# FRONT-UNIT.net
KiCad netlist of a schematic drawn in Altium Designer
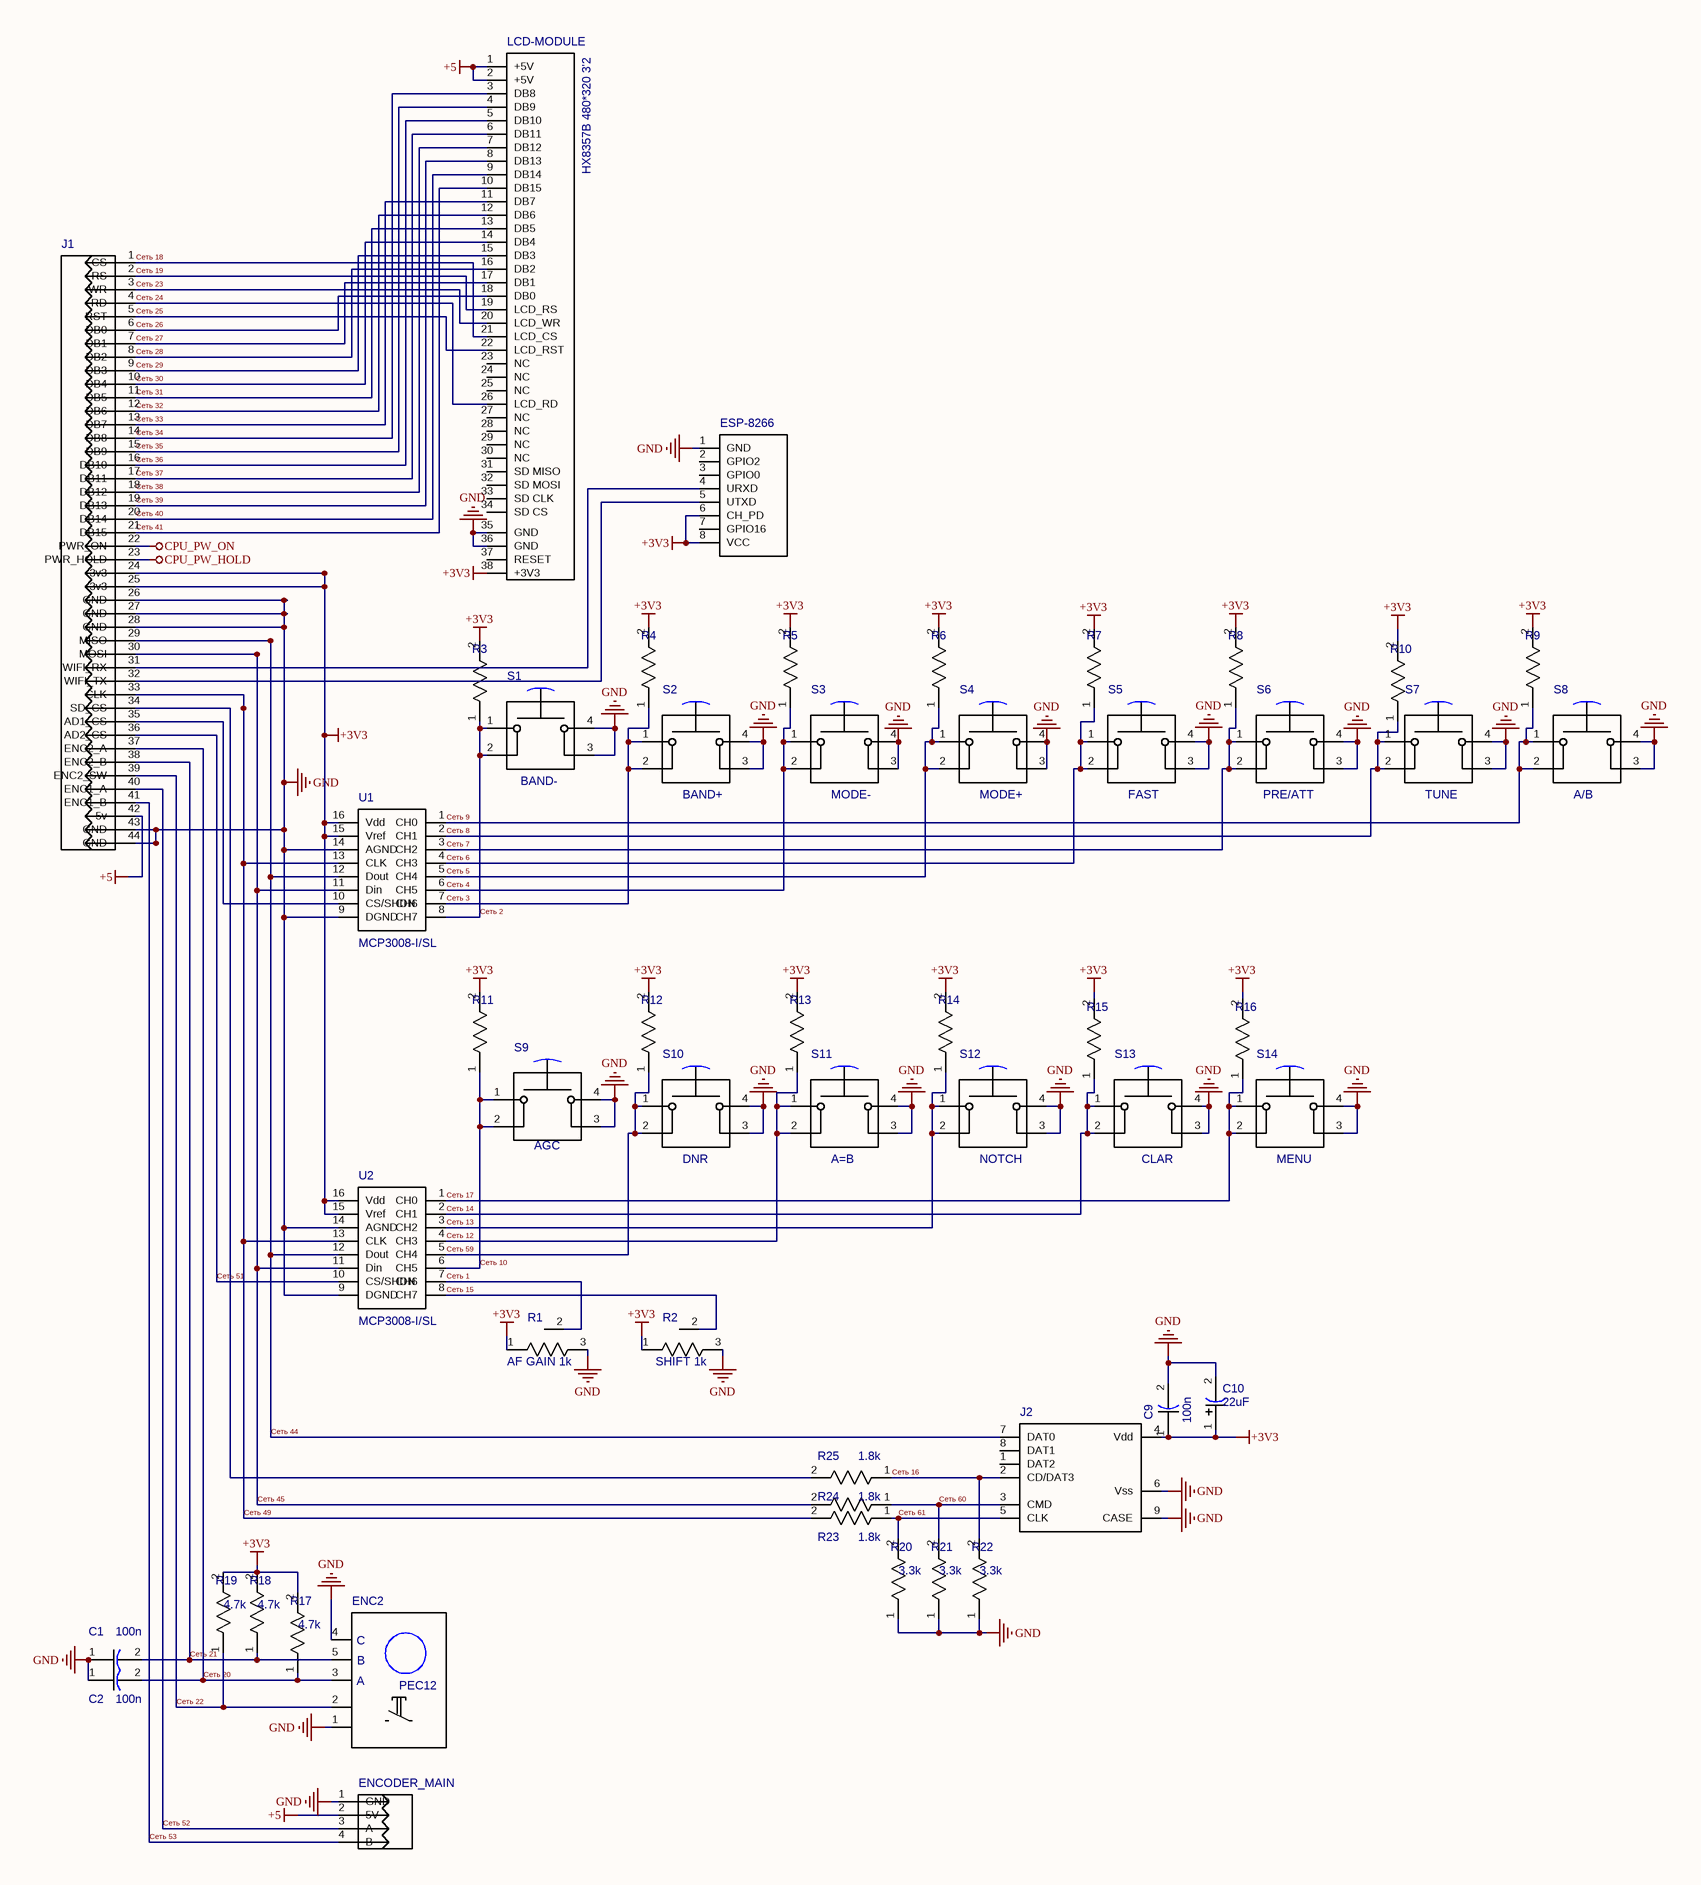
[diagram p0: FRONT-UNIT.SCHDOC, left]
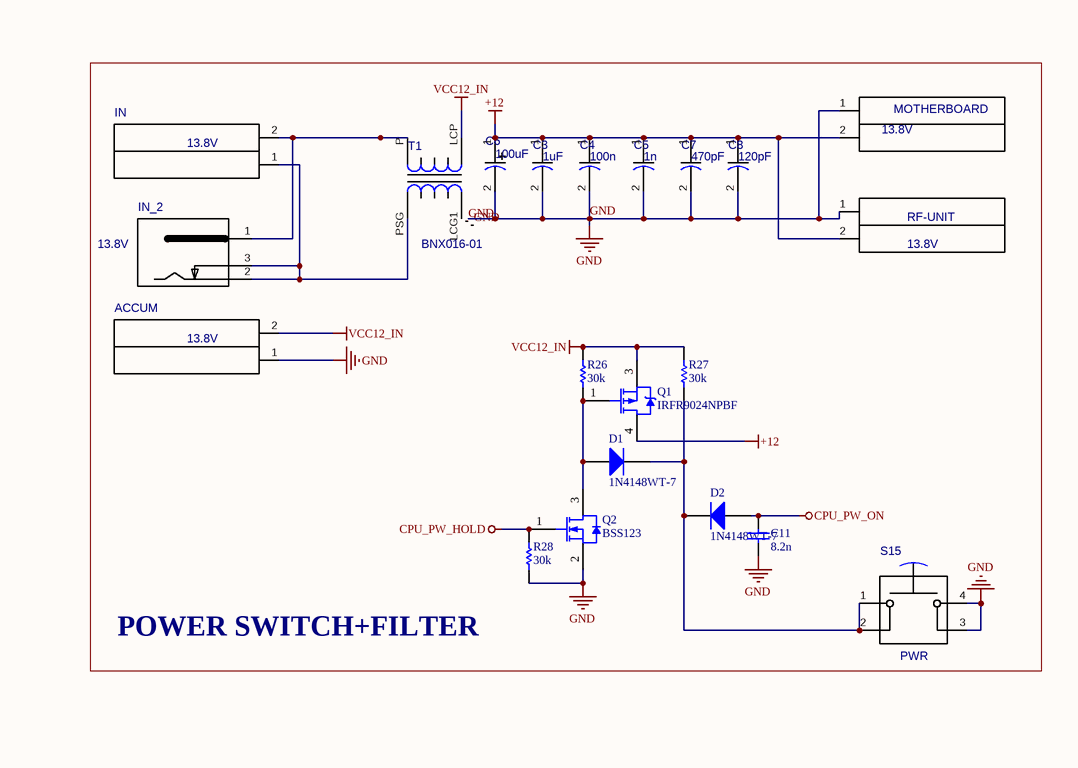
[diagram p1: FRONT-UNIT.SCHDOC, right]

(export (version "E")
  (design (tool "Eeschema 10.0.6"))
  (components
    (comp (ref "ACCUM")
      (value "13.8V")
      (footprint "JX2")
      (description "JX2")
      (libsource (lib "*") (part "JX2"))
    )
    (comp (ref "C1")
      (value "100n")
      (footprint "CAP_0805")
      (description "CAP_0805")
      (libsource (lib "*") (part "CAP_0805"))
    )
    (comp (ref "C2")
      (value "100n")
      (footprint "CAP_0805")
      (description "CAP_0805")
      (libsource (lib "*") (part "CAP_0805"))
    )
    (comp (ref "C3")
      (value "1uF")
      (footprint "CAP_1206")
      (description "CAP_1206")
      (libsource (lib "*") (part "CAP_1206"))
    )
    (comp (ref "C4")
      (value "100n")
      (footprint "CAP_1206")
      (description "CAP_1206")
      (libsource (lib "*") (part "CAP_1206"))
    )
    (comp (ref "C5")
      (value "1n")
      (footprint "CAP_1206")
      (description "CAP_1206")
      (libsource (lib "*") (part "CAP_1206"))
    )
    (comp (ref "C6")
      (value "100uF")
      (footprint "CAP250RP")
      (description "CAP250RP")
      (libsource (lib "*") (part "CAP250RP"))
    )
    (comp (ref "C7")
      (value "470pF")
      (footprint "CAP_1206")
      (description "CAP_1206")
      (libsource (lib "*") (part "CAP_1206"))
    )
    (comp (ref "C8")
      (value "120pF")
      (footprint "CAP_1206")
      (description "CAP_1206")
      (libsource (lib "*") (part "CAP_1206"))
    )
    (comp (ref "C9")
      (value "100n")
      (footprint "CAP_0805")
      (description "CAP_0805")
      (libsource (lib "*") (part "CAP_0805"))
    )
    (comp (ref "C10")
      (value "22uF")
      (footprint "EEEFC_sizeB")
      (description "EEEFC_sizeB")
      (libsource (lib "*") (part "EEEFC_sizeB"))
    )
    (comp (ref "C11")
      (value "8.2n")
      (footprint "CAPC2013X94X50LL20T25")
      (fields
        (field (name "MANUFACTURER") "AVX Interconnect / Elco")
        (field (name "PART NUMBER") "08055C822KAT2A")
      )
      (libsource (lib "Altium Content Vault") (part "CAP"))
    )
    (comp (ref "D1")
      (value "1N4148WT-7")
      (footprint "DIOD-SOD523-2_V")
      (description "Surface Mount Fast Switching Diode, -65 to 150 degC, 2-Pin SOD523, RoHS, Tape and Reel")
      (fields (field (name "MANUFACTURER") "Diodes Inc") (field (name "PARTNUMBER") "1N4148WT"))
      (libsource (lib "Altium Content Vault") (part "D-KA-2"))
    )
    (comp (ref "D2")
      (value "1N4148WT-7")
      (footprint "DIOD-SOD523-2_V")
      (description "Surface Mount Fast Switching Diode, -65 to 150 degC, 2-Pin SOD523, RoHS, Tape and Reel")
      (fields (field (name "MANUFACTURER") "Diodes Inc") (field (name "PARTNUMBER") "1N4148WT"))
      (libsource (lib "Altium Content Vault") (part "D-KA-2"))
    )
    (comp (ref "ENC2") (value "PEC12") (footprint "PEC12") (libsource (lib "*") (part "PEC12")))
    (comp (ref "ENCODER_MAIN")
      (value "644456-4")
      (footprint "644456-4")
      (libsource (lib "*") (part "644456-4"))
    )
    (comp (ref "ESP-8266")
      (value "ESP-01 ESP8266")
      (footprint "ESP-01 ESP8266")
      (libsource (lib "*") (part "ESP-01 ESP8266"))
    )
    (comp (ref "IN") (value "13.8V") (footprint "JX2") (description "JX2") (libsource (lib "*") (part "JX2")))
    (comp (ref "IN_2")
      (value "13.8V")
      (footprint "PJ-050B")
      (description "PJ-050B")
      (libsource (lib "*") (part "PJ-050B"))
    )
    (comp (ref "J1") (value "90131-0142") (footprint "90131-0142") (libsource (lib "*") (part "90131-0142")))
    (comp (ref "J2") (value "0472190001") (footprint "0472190001") (libsource (lib "*") (part "0472190001")))
    (comp (ref "LCD-MODULE")
      (value "HX8357B 480*320 3'2")
      (footprint "LCD-MODULE-3.2-480-320")
      (description "LCD-MODULE_3'2_480х320")
      (libsource (lib "FRONT-UNIT") (part "LCD-MODULE_3'2_480х320"))
    )
    (comp (ref "MOTHERBOARD")
      (value "13.8V")
      (footprint "JX2")
      (description "JX2")
      (libsource (lib "*") (part "JX2"))
    )
    (comp (ref "Q1")
      (value "IRFR9024NPBF")
      (footprint "ONSC-DPAK-3-369C-01_V")
      (description "IRFR9024NPBF, Транзистор, Р-канал 55В 11А")
      (fields (field (name "MANUFACTURER") "On Semiconductor") (field (name "PARTNUMBER") "NTD2955G"))
      (libsource (lib "Altium Content Vault") (part "ONSC-PMOS-G1S3D4-3_B"))
    )
    (comp (ref "Q2")
      (value "BSS123")
      (footprint "FAIR-SOT23-3_V")
      (fields (field (name "MANUFACTURER") "Fairchild"))
      (libsource (lib "Altium Content Vault") (part "NEMOS-GSD-3"))
    )
    (comp (ref "R1")
      (value "AF GAIN 1k")
      (footprint "PTV09")
      (description "Adjustable Resistor PTV09")
      (fields (field (name "Comment") "AF GAIN"))
      (libsource (lib "*") (part "PTV09"))
    )
    (comp (ref "R2")
      (value "SHIFT 1k")
      (footprint "PTV09")
      (description "Adjustable Resistor PTV09")
      (fields (field (name "Comment") "SHIFT"))
      (libsource (lib "*") (part "PTV09"))
    )
    (comp (ref "R3") (value "RES_0805") (footprint "RES_0805") (libsource (lib "*") (part "RES_0805")))
    (comp (ref "R4") (value "RES_0805") (footprint "RES_0805") (libsource (lib "*") (part "RES_0805")))
    (comp (ref "R5") (value "RES_0805") (footprint "RES_0805") (libsource (lib "*") (part "RES_0805")))
    (comp (ref "R6") (value "RES_0805") (footprint "RES_0805") (libsource (lib "*") (part "RES_0805")))
    (comp (ref "R7") (value "RES_0805") (footprint "RES_0805") (libsource (lib "*") (part "RES_0805")))
    (comp (ref "R8") (value "RES_0805") (footprint "RES_0805") (libsource (lib "*") (part "RES_0805")))
    (comp (ref "R9") (value "RES_0805") (footprint "RES_0805") (libsource (lib "*") (part "RES_0805")))
    (comp (ref "R10") (value "RES_0805") (footprint "RES_0805") (libsource (lib "*") (part "RES_0805")))
    (comp (ref "R11") (value "RES_0805") (footprint "RES_0805") (libsource (lib "*") (part "RES_0805")))
    (comp (ref "R12") (value "RES_0805") (footprint "RES_0805") (libsource (lib "*") (part "RES_0805")))
    (comp (ref "R13") (value "RES_0805") (footprint "RES_0805") (libsource (lib "*") (part "RES_0805")))
    (comp (ref "R14") (value "RES_0805") (footprint "RES_0805") (libsource (lib "*") (part "RES_0805")))
    (comp (ref "R15") (value "RES_0805") (footprint "RES_0805") (libsource (lib "*") (part "RES_0805")))
    (comp (ref "R16") (value "RES_0805") (footprint "RES_0805") (libsource (lib "*") (part "RES_0805")))
    (comp (ref "R17")
      (value "4.7k")
      (footprint "RES_0805")
      (description "RES_0805")
      (libsource (lib "*") (part "RES_0805"))
    )
    (comp (ref "R18")
      (value "4.7k")
      (footprint "RES_0805")
      (description "RES_0805")
      (libsource (lib "*") (part "RES_0805"))
    )
    (comp (ref "R19")
      (value "4.7k")
      (footprint "RES_0805")
      (description "RES_0805")
      (libsource (lib "*") (part "RES_0805"))
    )
    (comp (ref "R20")
      (value "3.3k")
      (footprint "RES_0805")
      (description "RES_0805")
      (libsource (lib "*") (part "RES_0805"))
    )
    (comp (ref "R21")
      (value "3.3k")
      (footprint "RES_0805")
      (description "RES_0805")
      (libsource (lib "*") (part "RES_0805"))
    )
    (comp (ref "R22")
      (value "3.3k")
      (footprint "RES_0805")
      (description "RES_0805")
      (libsource (lib "*") (part "RES_0805"))
    )
    (comp (ref "R23")
      (value "1.8k")
      (footprint "RES_0805")
      (description "RES_0805")
      (libsource (lib "*") (part "RES_0805"))
    )
    (comp (ref "R24")
      (value "1.8k")
      (footprint "RES_0805")
      (description "RES_0805")
      (libsource (lib "*") (part "RES_0805"))
    )
    (comp (ref "R25")
      (value "1.8k")
      (footprint "RES_0805")
      (description "RES_0805")
      (libsource (lib "*") (part "RES_0805"))
    )
    (comp (ref "R26")
      (value "30k")
      (footprint "RESC2013X60X40NL20T25")
      (fields (field (name "MANUFACTURER") "Panasonic") (field (name "PART NUMBER") "ERA-6AEB303V"))
      (libsource (lib "Altium Content Vault") (part "RES"))
    )
    (comp (ref "R27")
      (value "30k")
      (footprint "RESC2013X60X40NL20T25")
      (fields (field (name "MANUFACTURER") "Panasonic") (field (name "PART NUMBER") "ERA-6AEB303V"))
      (libsource (lib "Altium Content Vault") (part "RES"))
    )
    (comp (ref "R28")
      (value "30k")
      (footprint "RESC2013X60X40NL20T25")
      (fields (field (name "MANUFACTURER") "Panasonic") (field (name "PART NUMBER") "ERA-6AEB303V"))
      (libsource (lib "Altium Content Vault") (part "RES"))
    )
    (comp (ref "RF-UNIT")
      (value "13.8V")
      (footprint "JX2")
      (description "JX2")
      (libsource (lib "*") (part "JX2"))
    )
    (comp (ref "S1")
      (value "BAND-")
      (footprint "PTS645SK50LFS")
      (description "PTS645SK50LFS")
      (libsource (lib "*") (part "PTS645SK50LFS"))
    )
    (comp (ref "S2")
      (value "BAND+")
      (footprint "PTS645SK50LFS")
      (description "PTS645SK50LFS")
      (libsource (lib "*") (part "PTS645SK50LFS"))
    )
    (comp (ref "S3")
      (value "MODE-")
      (footprint "PTS645SK50LFS")
      (description "PTS645SK50LFS")
      (libsource (lib "*") (part "PTS645SK50LFS"))
    )
    (comp (ref "S4")
      (value "MODE+")
      (footprint "PTS645SK50LFS")
      (description "PTS645SK50LFS")
      (libsource (lib "*") (part "PTS645SK50LFS"))
    )
    (comp (ref "S5")
      (value "FAST")
      (footprint "PTS645SK50LFS")
      (description "PTS645SK50LFS")
      (libsource (lib "*") (part "PTS645SK50LFS"))
    )
    (comp (ref "S6")
      (value "PRE/ATT")
      (footprint "PTS645SK50LFS")
      (description "PTS645SK50LFS")
      (libsource (lib "*") (part "PTS645SK50LFS"))
    )
    (comp (ref "S7")
      (value "TUNE")
      (footprint "PTS645SK50LFS")
      (description "PTS645SK50LFS")
      (libsource (lib "*") (part "PTS645SK50LFS"))
    )
    (comp (ref "S8")
      (value "A/B")
      (footprint "PTS645SK50LFS")
      (description "PTS645SK50LFS")
      (libsource (lib "*") (part "PTS645SK50LFS"))
    )
    (comp (ref "S9")
      (value "AGC")
      (footprint "PTS645SK50LFS")
      (description "PTS645SK50LFS")
      (libsource (lib "*") (part "PTS645SK50LFS"))
    )
    (comp (ref "S10")
      (value "DNR")
      (footprint "PTS645SK50LFS")
      (description "PTS645SK50LFS")
      (libsource (lib "*") (part "PTS645SK50LFS"))
    )
    (comp (ref "S11")
      (value "A=B")
      (footprint "PTS645SK50LFS")
      (description "PTS645SK50LFS")
      (fields (field (name "Comment") "NOTCH"))
      (libsource (lib "*") (part "PTS645SK50LFS"))
    )
    (comp (ref "S12")
      (value "NOTCH")
      (footprint "PTS645SK50LFS")
      (description "PTS645SK50LFS")
      (libsource (lib "*") (part "PTS645SK50LFS"))
    )
    (comp (ref "S13")
      (value "CLAR")
      (footprint "PTS645SK50LFS")
      (description "PTS645SK50LFS")
      (libsource (lib "*") (part "PTS645SK50LFS"))
    )
    (comp (ref "S14")
      (value "MENU")
      (footprint "PTS645SK50LFS")
      (description "PTS645SK50LFS")
      (libsource (lib "*") (part "PTS645SK50LFS"))
    )
    (comp (ref "S15")
      (value "PWR")
      (footprint "PTS645SK50LFS")
      (description "PTS645SK50LFS")
      (libsource (lib "*") (part "PTS645SK50LFS"))
    )
    (comp (ref "T1")
      (value "BNX016-01")
      (footprint "TRANSF_ICORE")
      (description "Transformer")
      (fields (field (name "Comment") "TRANSF_ICORE"))
      (libsource (lib "*") (part "TRANSF_ICORE"))
    )
    (comp (ref "U1")
      (value "MCP3008-I/SL")
      (footprint "MCP3008-I/SL")
      (libsource (lib "*") (part "MCP3008-I/SL"))
    )
    (comp (ref "U2")
      (value "MCP3008-I/SL")
      (footprint "MCP3008-I/SL")
      (libsource (lib "*") (part "MCP3008-I/SL"))
    )
  )
  (nets
    (net (code "1") (name "+3V3") (class "Default")
      (node (ref "C10") (pin "1") (pinfunction "PLUS_1") (pintype "passive"))
      (node (ref "C9") (pin "1") (pinfunction "1_1") (pintype "passive"))
      (node (ref "ESP-8266") (pin "6") (pinfunction "CH_PD_6") (pintype "passive"))
      (node (ref "ESP-8266") (pin "8") (pinfunction "VCC_8") (pintype "passive"))
      (node (ref "J1") (pin "24") (pinfunction "3v3_24") (pintype "passive"))
      (node (ref "J1") (pin "25") (pinfunction "3v3_25") (pintype "passive"))
      (node (ref "J2") (pin "4") (pinfunction "Vdd_4") (pintype "passive"))
      (node (ref "LCD-MODULE") (pin "38") (pinfunction "+3V3_38") (pintype "passive"))
      (node (ref "R1") (pin "1") (pinfunction "CW_1") (pintype "passive"))
      (node (ref "R10") (pin "2") (pinfunction "2_2") (pintype "passive"))
      (node (ref "R11") (pin "2") (pinfunction "2_2") (pintype "passive"))
      (node (ref "R12") (pin "2") (pinfunction "2_2") (pintype "passive"))
      (node (ref "R13") (pin "2") (pinfunction "2_2") (pintype "passive"))
      (node (ref "R14") (pin "2") (pinfunction "2_2") (pintype "passive"))
      (node (ref "R15") (pin "2") (pinfunction "2_2") (pintype "passive"))
      (node (ref "R16") (pin "2") (pinfunction "2_2") (pintype "passive"))
      (node (ref "R17") (pin "2") (pinfunction "2_2") (pintype "passive"))
      (node (ref "R18") (pin "2") (pinfunction "2_2") (pintype "passive"))
      (node (ref "R19") (pin "2") (pinfunction "2_2") (pintype "passive"))
      (node (ref "R2") (pin "1") (pinfunction "CW_1") (pintype "passive"))
      (node (ref "R3") (pin "2") (pinfunction "2_2") (pintype "passive"))
      (node (ref "R4") (pin "2") (pinfunction "2_2") (pintype "passive"))
      (node (ref "R5") (pin "2") (pinfunction "2_2") (pintype "passive"))
      (node (ref "R6") (pin "2") (pinfunction "2_2") (pintype "passive"))
      (node (ref "R7") (pin "2") (pinfunction "2_2") (pintype "passive"))
      (node (ref "R8") (pin "2") (pinfunction "2_2") (pintype "passive"))
      (node (ref "R9") (pin "2") (pinfunction "2_2") (pintype "passive"))
      (node (ref "U1") (pin "15") (pinfunction "Vref_15") (pintype "passive"))
      (node (ref "U1") (pin "16") (pinfunction "Vdd_16") (pintype "passive"))
      (node (ref "U2") (pin "15") (pinfunction "Vref_15") (pintype "passive"))
      (node (ref "U2") (pin "16") (pinfunction "Vdd_16") (pintype "passive"))
    )
    (net (code "2") (name "+5") (class "Default")
      (node (ref "ENCODER_MAIN") (pin "2") (pinfunction "5V_2") (pintype "passive"))
      (node (ref "J1") (pin "42") (pinfunction "5v_42") (pintype "passive"))
      (node (ref "LCD-MODULE") (pin "1") (pinfunction "+5V_1") (pintype "passive"))
      (node (ref "LCD-MODULE") (pin "2") (pinfunction "+5V_2") (pintype "passive"))
    )
    (net (code "3") (name "+12") (class "Default")
      (node (ref "C3") (pin "1") (pinfunction "1_1") (pintype "passive"))
      (node (ref "C4") (pin "1") (pinfunction "1_1") (pintype "passive"))
      (node (ref "C5") (pin "1") (pinfunction "1_1") (pintype "passive"))
      (node (ref "C6") (pin "1") (pinfunction "PLUS_1") (pintype "passive"))
      (node (ref "C7") (pin "1") (pinfunction "1_1") (pintype "passive"))
      (node (ref "C8") (pin "1") (pinfunction "1_1") (pintype "passive"))
      (node (ref "MOTHERBOARD") (pin "2") (pinfunction "1_2") (pintype "passive"))
      (node (ref "Q1") (pin "4") (pinfunction "D_4") (pintype "passive"))
      (node (ref "RF-UNIT") (pin "2") (pinfunction "1_2") (pintype "passive"))
    )
    (net (code "4") (name "/Сеть 1") (class "Default")
      (node (ref "R1") (pin "2") (pinfunction "W_2") (pintype "passive"))
      (node (ref "U2") (pin "7") (pinfunction "CH6_7") (pintype "passive"))
    )
    (net (code "5") (name "/Сеть 2") (class "Default")
      (node (ref "R3") (pin "1") (pinfunction "1_1") (pintype "passive"))
      (node (ref "S1") (pin "1") (pinfunction "A_1") (pintype "passive"))
      (node (ref "S1") (pin "2") (pinfunction "A_2") (pintype "passive"))
      (node (ref "U1") (pin "8") (pinfunction "CH7_8") (pintype "passive"))
    )
    (net (code "6") (name "/Сеть 3") (class "Default")
      (node (ref "R4") (pin "1") (pinfunction "1_1") (pintype "passive"))
      (node (ref "S2") (pin "1") (pinfunction "A_1") (pintype "passive"))
      (node (ref "S2") (pin "2") (pinfunction "A_2") (pintype "passive"))
      (node (ref "U1") (pin "7") (pinfunction "CH6_7") (pintype "passive"))
    )
    (net (code "7") (name "/Сеть 4") (class "Default")
      (node (ref "R5") (pin "1") (pinfunction "1_1") (pintype "passive"))
      (node (ref "S3") (pin "1") (pinfunction "A_1") (pintype "passive"))
      (node (ref "S3") (pin "2") (pinfunction "A_2") (pintype "passive"))
      (node (ref "U1") (pin "6") (pinfunction "CH5_6") (pintype "passive"))
    )
    (net (code "8") (name "/Сеть 5") (class "Default")
      (node (ref "R6") (pin "1") (pinfunction "1_1") (pintype "passive"))
      (node (ref "S4") (pin "1") (pinfunction "A_1") (pintype "passive"))
      (node (ref "S4") (pin "2") (pinfunction "A_2") (pintype "passive"))
      (node (ref "U1") (pin "5") (pinfunction "CH4_5") (pintype "passive"))
    )
    (net (code "9") (name "/Сеть 6") (class "Default")
      (node (ref "R7") (pin "1") (pinfunction "1_1") (pintype "passive"))
      (node (ref "S5") (pin "1") (pinfunction "A_1") (pintype "passive"))
      (node (ref "S5") (pin "2") (pinfunction "A_2") (pintype "passive"))
      (node (ref "U1") (pin "4") (pinfunction "CH3_4") (pintype "passive"))
    )
    (net (code "10") (name "/Сеть 7") (class "Default")
      (node (ref "R8") (pin "1") (pinfunction "1_1") (pintype "passive"))
      (node (ref "S6") (pin "1") (pinfunction "A_1") (pintype "passive"))
      (node (ref "S6") (pin "2") (pinfunction "A_2") (pintype "passive"))
      (node (ref "U1") (pin "3") (pinfunction "CH2_3") (pintype "passive"))
    )
    (net (code "11") (name "/Сеть 8") (class "Default")
      (node (ref "R10") (pin "1") (pinfunction "1_1") (pintype "passive"))
      (node (ref "S7") (pin "1") (pinfunction "A_1") (pintype "passive"))
      (node (ref "S7") (pin "2") (pinfunction "A_2") (pintype "passive"))
      (node (ref "U1") (pin "2") (pinfunction "CH1_2") (pintype "passive"))
    )
    (net (code "12") (name "/Сеть 9") (class "Default")
      (node (ref "R9") (pin "1") (pinfunction "1_1") (pintype "passive"))
      (node (ref "S8") (pin "1") (pinfunction "A_1") (pintype "passive"))
      (node (ref "S8") (pin "2") (pinfunction "A_2") (pintype "passive"))
      (node (ref "U1") (pin "1") (pinfunction "CH0_1") (pintype "passive"))
    )
    (net (code "13") (name "/Сеть 10") (class "Default")
      (node (ref "R11") (pin "1") (pinfunction "1_1") (pintype "passive"))
      (node (ref "S9") (pin "1") (pinfunction "A_1") (pintype "passive"))
      (node (ref "S9") (pin "2") (pinfunction "A_2") (pintype "passive"))
      (node (ref "U2") (pin "6") (pinfunction "CH5_6") (pintype "passive"))
    )
    (net (code "14") (name "/Сеть 12") (class "Default")
      (node (ref "R13") (pin "1") (pinfunction "1_1") (pintype "passive"))
      (node (ref "S11") (pin "1") (pinfunction "A_1") (pintype "passive"))
      (node (ref "S11") (pin "2") (pinfunction "A_2") (pintype "passive"))
      (node (ref "U2") (pin "4") (pinfunction "CH3_4") (pintype "passive"))
    )
    (net (code "15") (name "/Сеть 13") (class "Default")
      (node (ref "R14") (pin "1") (pinfunction "1_1") (pintype "passive"))
      (node (ref "S12") (pin "1") (pinfunction "A_1") (pintype "passive"))
      (node (ref "S12") (pin "2") (pinfunction "A_2") (pintype "passive"))
      (node (ref "U2") (pin "3") (pinfunction "CH2_3") (pintype "passive"))
    )
    (net (code "16") (name "/Сеть 14") (class "Default")
      (node (ref "R15") (pin "1") (pinfunction "1_1") (pintype "passive"))
      (node (ref "S13") (pin "1") (pinfunction "A_1") (pintype "passive"))
      (node (ref "S13") (pin "2") (pinfunction "A_2") (pintype "passive"))
      (node (ref "U2") (pin "2") (pinfunction "CH1_2") (pintype "passive"))
    )
    (net (code "17") (name "/Сеть 15") (class "Default")
      (node (ref "R2") (pin "2") (pinfunction "W_2") (pintype "passive"))
      (node (ref "U2") (pin "8") (pinfunction "CH7_8") (pintype "passive"))
    )
    (net (code "18") (name "/Сеть 16") (class "Default")
      (node (ref "J2") (pin "2") (pinfunction "CD/DAT3_2") (pintype "passive"))
      (node (ref "R22") (pin "2") (pinfunction "2_2") (pintype "passive"))
      (node (ref "R25") (pin "1") (pinfunction "1_1") (pintype "passive"))
    )
    (net (code "19") (name "/Сеть 17") (class "Default")
      (node (ref "R16") (pin "1") (pinfunction "1_1") (pintype "passive"))
      (node (ref "S14") (pin "1") (pinfunction "A_1") (pintype "passive"))
      (node (ref "S14") (pin "2") (pinfunction "A_2") (pintype "passive"))
      (node (ref "U2") (pin "1") (pinfunction "CH0_1") (pintype "passive"))
    )
    (net (code "20") (name "/Сеть 18") (class "Default")
      (node (ref "J1") (pin "1") (pinfunction "CS_1") (pintype "passive"))
      (node (ref "LCD-MODULE") (pin "21") (pinfunction "LCD_CS_21") (pintype "passive"))
    )
    (net (code "21") (name "/Сеть 19") (class "Default")
      (node (ref "J1") (pin "2") (pinfunction "RS_2") (pintype "passive"))
      (node (ref "LCD-MODULE") (pin "19") (pinfunction "LCD_RS_19") (pintype "passive"))
    )
    (net (code "22") (name "/Сеть 20") (class "Default")
      (node (ref "C2") (pin "2") (pinfunction "2_2") (pintype "passive"))
      (node (ref "ENC2") (pin "3") (pinfunction "A_3") (pintype "passive"))
      (node (ref "J1") (pin "37") (pinfunction "ENC2_A_37") (pintype "passive"))
      (node (ref "R17") (pin "1") (pinfunction "1_1") (pintype "passive"))
    )
    (net (code "23") (name "/Сеть 21") (class "Default")
      (node (ref "C1") (pin "2") (pinfunction "2_2") (pintype "passive"))
      (node (ref "ENC2") (pin "5") (pinfunction "B_5") (pintype "passive"))
      (node (ref "J1") (pin "38") (pinfunction "ENC2_B_38") (pintype "passive"))
      (node (ref "R18") (pin "1") (pinfunction "1_1") (pintype "passive"))
    )
    (net (code "24") (name "/Сеть 22") (class "Default")
      (node (ref "ENC2") (pin "2") (pinfunction "2_2") (pintype "passive"))
      (node (ref "J1") (pin "39") (pinfunction "ENC2_SW_39") (pintype "passive"))
      (node (ref "R19") (pin "1") (pinfunction "1_1") (pintype "passive"))
    )
    (net (code "25") (name "/Сеть 23") (class "Default")
      (node (ref "J1") (pin "3") (pinfunction "WR_3") (pintype "passive"))
      (node (ref "LCD-MODULE") (pin "20") (pinfunction "LCD_WR_20") (pintype "passive"))
    )
    (net (code "26") (name "/Сеть 24") (class "Default")
      (node (ref "J1") (pin "4") (pinfunction "RD_4") (pintype "passive"))
      (node (ref "LCD-MODULE") (pin "26") (pinfunction "LCD_RD_26") (pintype "passive"))
    )
    (net (code "27") (name "/Сеть 25") (class "Default")
      (node (ref "J1") (pin "5") (pinfunction "RST_5") (pintype "passive"))
      (node (ref "LCD-MODULE") (pin "22") (pinfunction "LCD_RST_22") (pintype "passive"))
    )
    (net (code "28") (name "/Сеть 26") (class "Default")
      (node (ref "J1") (pin "6") (pinfunction "DB0_6") (pintype "passive"))
      (node (ref "LCD-MODULE") (pin "18") (pinfunction "DB0_18") (pintype "passive"))
    )
    (net (code "29") (name "/Сеть 27") (class "Default")
      (node (ref "J1") (pin "7") (pinfunction "DB1_7") (pintype "passive"))
      (node (ref "LCD-MODULE") (pin "17") (pinfunction "DB1_17") (pintype "passive"))
    )
    (net (code "30") (name "/Сеть 28") (class "Default")
      (node (ref "J1") (pin "8") (pinfunction "DB2_8") (pintype "passive"))
      (node (ref "LCD-MODULE") (pin "16") (pinfunction "DB2_16") (pintype "passive"))
    )
    (net (code "31") (name "/Сеть 29") (class "Default")
      (node (ref "J1") (pin "9") (pinfunction "DB3_9") (pintype "passive"))
      (node (ref "LCD-MODULE") (pin "15") (pinfunction "DB3_15") (pintype "passive"))
    )
    (net (code "32") (name "/Сеть 30") (class "Default")
      (node (ref "J1") (pin "10") (pinfunction "DB4_10") (pintype "passive"))
      (node (ref "LCD-MODULE") (pin "14") (pinfunction "DB4_14") (pintype "passive"))
    )
    (net (code "33") (name "/Сеть 31") (class "Default")
      (node (ref "J1") (pin "11") (pinfunction "DB5_11") (pintype "passive"))
      (node (ref "LCD-MODULE") (pin "13") (pinfunction "DB5_13") (pintype "passive"))
    )
    (net (code "34") (name "/Сеть 32") (class "Default")
      (node (ref "J1") (pin "12") (pinfunction "DB6_12") (pintype "passive"))
      (node (ref "LCD-MODULE") (pin "12") (pinfunction "DB6_12") (pintype "passive"))
    )
    (net (code "35") (name "/Сеть 33") (class "Default")
      (node (ref "J1") (pin "13") (pinfunction "DB7_13") (pintype "passive"))
      (node (ref "LCD-MODULE") (pin "11") (pinfunction "DB7_11") (pintype "passive"))
    )
    (net (code "36") (name "/Сеть 34") (class "Default")
      (node (ref "J1") (pin "14") (pinfunction "DB8_14") (pintype "passive"))
      (node (ref "LCD-MODULE") (pin "3") (pinfunction "DB8_3") (pintype "passive"))
    )
    (net (code "37") (name "/Сеть 35") (class "Default")
      (node (ref "J1") (pin "15") (pinfunction "DB9_15") (pintype "passive"))
      (node (ref "LCD-MODULE") (pin "4") (pinfunction "DB9_4") (pintype "passive"))
    )
    (net (code "38") (name "/Сеть 36") (class "Default")
      (node (ref "J1") (pin "16") (pinfunction "DB10_16") (pintype "passive"))
      (node (ref "LCD-MODULE") (pin "5") (pinfunction "DB10_5") (pintype "passive"))
    )
    (net (code "39") (name "/Сеть 37") (class "Default")
      (node (ref "J1") (pin "17") (pinfunction "DB11_17") (pintype "passive"))
      (node (ref "LCD-MODULE") (pin "6") (pinfunction "DB11_6") (pintype "passive"))
    )
    (net (code "40") (name "/Сеть 38") (class "Default")
      (node (ref "J1") (pin "18") (pinfunction "DB12_18") (pintype "passive"))
      (node (ref "LCD-MODULE") (pin "7") (pinfunction "DB12_7") (pintype "passive"))
    )
    (net (code "41") (name "/Сеть 39") (class "Default")
      (node (ref "J1") (pin "19") (pinfunction "DB13_19") (pintype "passive"))
      (node (ref "LCD-MODULE") (pin "8") (pinfunction "DB13_8") (pintype "passive"))
    )
    (net (code "42") (name "/Сеть 40") (class "Default")
      (node (ref "J1") (pin "20") (pinfunction "DB14_20") (pintype "passive"))
      (node (ref "LCD-MODULE") (pin "9") (pinfunction "DB14_9") (pintype "passive"))
    )
    (net (code "43") (name "/Сеть 41") (class "Default")
      (node (ref "J1") (pin "21") (pinfunction "DB15_21") (pintype "passive"))
      (node (ref "LCD-MODULE") (pin "10") (pinfunction "DB15_10") (pintype "passive"))
    )
    (net (code "44") (name "/Сеть 44") (class "Default")
      (node (ref "J1") (pin "29") (pinfunction "MISO_29") (pintype "passive"))
      (node (ref "J2") (pin "7") (pinfunction "DAT0_7") (pintype "passive"))
      (node (ref "U1") (pin "12") (pinfunction "Dout_12") (pintype "passive"))
      (node (ref "U2") (pin "12") (pinfunction "Dout_12") (pintype "passive"))
    )
    (net (code "45") (name "/Сеть 45") (class "Default")
      (node (ref "J1") (pin "30") (pinfunction "MOSI_30") (pintype "passive"))
      (node (ref "R24") (pin "2") (pinfunction "2_2") (pintype "passive"))
      (node (ref "U1") (pin "11") (pinfunction "Din_11") (pintype "passive"))
      (node (ref "U2") (pin "11") (pinfunction "Din_11") (pintype "passive"))
    )
    (net (code "46") (name "/Сеть 49") (class "Default")
      (node (ref "J1") (pin "33") (pinfunction "CLK_33") (pintype "passive"))
      (node (ref "R23") (pin "2") (pinfunction "2_2") (pintype "passive"))
      (node (ref "U1") (pin "13") (pinfunction "CLK_13") (pintype "passive"))
      (node (ref "U2") (pin "13") (pinfunction "CLK_13") (pintype "passive"))
    )
    (net (code "47") (name "/Сеть 51") (class "Default")
      (node (ref "J1") (pin "36") (pinfunction "AD2_CS_36") (pintype "passive"))
      (node (ref "U2") (pin "10") (pinfunction "CS/SHDN_10") (pintype "passive"))
    )
    (net (code "48") (name "/Сеть 52") (class "Default")
      (node (ref "ENCODER_MAIN") (pin "3") (pinfunction "A_3") (pintype "passive"))
      (node (ref "J1") (pin "40") (pinfunction "ENC1_A_40") (pintype "passive"))
    )
    (net (code "49") (name "/Сеть 53") (class "Default")
      (node (ref "ENCODER_MAIN") (pin "4") (pinfunction "B_4") (pintype "passive"))
      (node (ref "J1") (pin "41") (pinfunction "ENC1_B_41") (pintype "passive"))
    )
    (net (code "50") (name "/Сеть 59") (class "Default")
      (node (ref "R12") (pin "1") (pinfunction "1_1") (pintype "passive"))
      (node (ref "S10") (pin "1") (pinfunction "A_1") (pintype "passive"))
      (node (ref "S10") (pin "2") (pinfunction "A_2") (pintype "passive"))
      (node (ref "U2") (pin "5") (pinfunction "CH4_5") (pintype "passive"))
    )
    (net (code "51") (name "/Сеть 60") (class "Default")
      (node (ref "J2") (pin "3") (pinfunction "CMD_3") (pintype "passive"))
      (node (ref "R21") (pin "2") (pinfunction "2_2") (pintype "passive"))
      (node (ref "R24") (pin "1") (pinfunction "1_1") (pintype "passive"))
    )
    (net (code "52") (name "/Сеть 61") (class "Default")
      (node (ref "J2") (pin "5") (pinfunction "CLK_5") (pintype "passive"))
      (node (ref "R20") (pin "2") (pinfunction "2_2") (pintype "passive"))
      (node (ref "R23") (pin "1") (pinfunction "1_1") (pintype "passive"))
    )
    (net (code "53") (name "CPU_PW_HOLD") (class "Default")
      (node (ref "J1") (pin "23") (pinfunction "PWR_HOLD_23") (pintype "passive"))
      (node (ref "Q2") (pin "1") (pinfunction "G_1") (pintype "passive"))
      (node (ref "R28") (pin "2") (pinfunction "2_2") (pintype "passive"))
    )
    (net (code "54") (name "CPU_PW_ON") (class "Default")
      (node (ref "C11") (pin "2") (pinfunction "2_2") (pintype "passive"))
      (node (ref "D2") (pin "2") (pinfunction "A_2") (pintype "passive"))
      (node (ref "J1") (pin "22") (pinfunction "PWR_ON_22") (pintype "passive"))
    )
    (net (code "55") (name "GND") (class "Default")
      (node (ref "ACCUM") (pin "1") (pinfunction "2_1") (pintype "passive"))
      (node (ref "C1") (pin "1") (pinfunction "1_1") (pintype "passive"))
      (node (ref "C10") (pin "2") (pinfunction "MINUS_2") (pintype "passive"))
      (node (ref "C11") (pin "1") (pinfunction "1_1") (pintype "passive"))
      (node (ref "C2") (pin "1") (pinfunction "1_1") (pintype "passive"))
      (node (ref "C3") (pin "2") (pinfunction "2_2") (pintype "passive"))
      (node (ref "C4") (pin "2") (pinfunction "2_2") (pintype "passive"))
      (node (ref "C5") (pin "2") (pinfunction "2_2") (pintype "passive"))
      (node (ref "C6") (pin "2") (pinfunction "MINUS_2") (pintype "passive"))
      (node (ref "C7") (pin "2") (pinfunction "2_2") (pintype "passive"))
      (node (ref "C8") (pin "2") (pinfunction "2_2") (pintype "passive"))
      (node (ref "C9") (pin "2") (pinfunction "2_2") (pintype "passive"))
      (node (ref "ENC2") (pin "1") (pinfunction "1_1") (pintype "passive"))
      (node (ref "ENC2") (pin "4") (pinfunction "C_4") (pintype "passive"))
      (node (ref "ENCODER_MAIN") (pin "1") (pinfunction "GND_1") (pintype "passive"))
      (node (ref "ESP-8266") (pin "1") (pinfunction "GND_1") (pintype "passive"))
      (node (ref "J1") (pin "26") (pinfunction "GND_26") (pintype "passive"))
      (node (ref "J1") (pin "27") (pinfunction "GND_27") (pintype "passive"))
      (node (ref "J1") (pin "28") (pinfunction "GND_28") (pintype "passive"))
      (node (ref "J1") (pin "43") (pinfunction "GND_43") (pintype "passive"))
      (node (ref "J1") (pin "44") (pinfunction "GND_44") (pintype "passive"))
      (node (ref "J2") (pin "6") (pinfunction "Vss_6") (pintype "passive"))
      (node (ref "J2") (pin "9") (pinfunction "CASE_9") (pintype "passive"))
      (node (ref "LCD-MODULE") (pin "35") (pinfunction "GND_35") (pintype "passive"))
      (node (ref "LCD-MODULE") (pin "36") (pinfunction "GND_36") (pintype "passive"))
      (node (ref "MOTHERBOARD") (pin "1") (pinfunction "2_1") (pintype "passive"))
      (node (ref "Q2") (pin "2") (pinfunction "S_2") (pintype "passive"))
      (node (ref "R1") (pin "3") (pinfunction "CCW_3") (pintype "passive"))
      (node (ref "R2") (pin "3") (pinfunction "CCW_3") (pintype "passive"))
      (node (ref "R20") (pin "1") (pinfunction "1_1") (pintype "passive"))
      (node (ref "R21") (pin "1") (pinfunction "1_1") (pintype "passive"))
      (node (ref "R22") (pin "1") (pinfunction "1_1") (pintype "passive"))
      (node (ref "R28") (pin "1") (pinfunction "1_1") (pintype "passive"))
      (node (ref "RF-UNIT") (pin "1") (pinfunction "2_1") (pintype "passive"))
      (node (ref "S1") (pin "3") (pinfunction "B_3") (pintype "passive"))
      (node (ref "S1") (pin "4") (pinfunction "B_4") (pintype "passive"))
      (node (ref "S10") (pin "3") (pinfunction "B_3") (pintype "passive"))
      (node (ref "S10") (pin "4") (pinfunction "B_4") (pintype "passive"))
      (node (ref "S11") (pin "3") (pinfunction "B_3") (pintype "passive"))
      (node (ref "S11") (pin "4") (pinfunction "B_4") (pintype "passive"))
      (node (ref "S12") (pin "3") (pinfunction "B_3") (pintype "passive"))
      (node (ref "S12") (pin "4") (pinfunction "B_4") (pintype "passive"))
      (node (ref "S13") (pin "3") (pinfunction "B_3") (pintype "passive"))
      (node (ref "S13") (pin "4") (pinfunction "B_4") (pintype "passive"))
      (node (ref "S14") (pin "3") (pinfunction "B_3") (pintype "passive"))
      (node (ref "S14") (pin "4") (pinfunction "B_4") (pintype "passive"))
      (node (ref "S15") (pin "3") (pinfunction "B_3") (pintype "passive"))
      (node (ref "S15") (pin "4") (pinfunction "B_4") (pintype "passive"))
      (node (ref "S2") (pin "3") (pinfunction "B_3") (pintype "passive"))
      (node (ref "S2") (pin "4") (pinfunction "B_4") (pintype "passive"))
      (node (ref "S3") (pin "3") (pinfunction "B_3") (pintype "passive"))
      (node (ref "S3") (pin "4") (pinfunction "B_4") (pintype "passive"))
      (node (ref "S4") (pin "3") (pinfunction "B_3") (pintype "passive"))
      (node (ref "S4") (pin "4") (pinfunction "B_4") (pintype "passive"))
      (node (ref "S5") (pin "3") (pinfunction "B_3") (pintype "passive"))
      (node (ref "S5") (pin "4") (pinfunction "B_4") (pintype "passive"))
      (node (ref "S6") (pin "3") (pinfunction "B_3") (pintype "passive"))
      (node (ref "S6") (pin "4") (pinfunction "B_4") (pintype "passive"))
      (node (ref "S7") (pin "3") (pinfunction "B_3") (pintype "passive"))
      (node (ref "S7") (pin "4") (pinfunction "B_4") (pintype "passive"))
      (node (ref "S8") (pin "3") (pinfunction "B_3") (pintype "passive"))
      (node (ref "S8") (pin "4") (pinfunction "B_4") (pintype "passive"))
      (node (ref "S9") (pin "3") (pinfunction "B_3") (pintype "passive"))
      (node (ref "S9") (pin "4") (pinfunction "B_4") (pintype "passive"))
      (node (ref "T1") (pin "LCG2") (pinfunction "0_LCG2") (pintype "passive"))
      (node (ref "T1") (pin "LCG3") (pinfunction "0_LCG3") (pintype "passive"))
      (node (ref "U1") (pin "14") (pinfunction "AGND_14") (pintype "passive"))
      (node (ref "U1") (pin "9") (pinfunction "DGND_9") (pintype "passive"))
      (node (ref "U2") (pin "14") (pinfunction "AGND_14") (pintype "passive"))
      (node (ref "U2") (pin "9") (pinfunction "DGND_9") (pintype "passive"))
    )
    (net (code "56") (name "Net-(D1-A)") (class "Default")
      (node (ref "D1") (pin "2") (pinfunction "A_2") (pintype "passive"))
      (node (ref "Q1") (pin "1") (pinfunction "G_1") (pintype "passive"))
      (node (ref "Q2") (pin "3") (pinfunction "D_3") (pintype "passive"))
      (node (ref "R26") (pin "1") (pinfunction "1_1") (pintype "passive"))
    )
    (net (code "57") (name "Net-(D1-K)") (class "Default")
      (node (ref "D1") (pin "1") (pinfunction "K_1") (pintype "passive"))
      (node (ref "D2") (pin "1") (pinfunction "K_1") (pintype "passive"))
      (node (ref "R27") (pin "1") (pinfunction "1_1") (pintype "passive"))
      (node (ref "S15") (pin "1") (pinfunction "A_1") (pintype "passive"))
      (node (ref "S15") (pin "2") (pinfunction "A_2") (pintype "passive"))
    )
    (net (code "58") (name "Net-(ESP-8266-URXD)") (class "Default")
      (node (ref "ESP-8266") (pin "4") (pinfunction "URXD_4") (pintype "passive"))
      (node (ref "J1") (pin "31") (pinfunction "WIFI_RX_31") (pintype "passive"))
    )
    (net (code "59") (name "Net-(ESP-8266-UTXD)") (class "Default")
      (node (ref "ESP-8266") (pin "5") (pinfunction "UTXD_5") (pintype "passive"))
      (node (ref "J1") (pin "32") (pinfunction "WIFI_TX_32") (pintype "passive"))
    )
    (net (code "60") (name "Net-(IN-1)") (class "Default")
      (node (ref "IN") (pin "2") (pinfunction "1_2") (pintype "passive"))
      (node (ref "IN_2") (pin "1") (pinfunction "1_1") (pintype "passive"))
      (node (ref "T1") (pin "P") (pinfunction "P1_P") (pintype "passive"))
    )
    (net (code "61") (name "Net-(IN-2)") (class "Default")
      (node (ref "IN") (pin "1") (pinfunction "2_1") (pintype "passive"))
      (node (ref "IN_2") (pin "2") (pinfunction "2_2") (pintype "passive"))
      (node (ref "IN_2") (pin "3") (pinfunction "3_3") (pintype "passive"))
      (node (ref "T1") (pin "PSG") (pinfunction "S1_PSG") (pintype "passive"))
    )
    (net (code "62") (name "Net-(J1-AD1_CS)") (class "Default")
      (node (ref "J1") (pin "35") (pinfunction "AD1_CS_35") (pintype "passive"))
      (node (ref "U1") (pin "10") (pinfunction "CS/SHDN_10") (pintype "passive"))
    )
    (net (code "63") (name "Net-(J1-SD_CS)") (class "Default")
      (node (ref "J1") (pin "34") (pinfunction "SD_CS_34") (pintype "passive"))
      (node (ref "R25") (pin "2") (pinfunction "2_2") (pintype "passive"))
    )
    (net (code "64") (name "VCC12_IN") (class "Default")
      (node (ref "ACCUM") (pin "2") (pinfunction "1_2") (pintype "passive"))
      (node (ref "Q1") (pin "3") (pinfunction "S_3") (pintype "passive"))
      (node (ref "R26") (pin "2") (pinfunction "2_2") (pintype "passive"))
      (node (ref "R27") (pin "2") (pinfunction "2_2") (pintype "passive"))
      (node (ref "T1") (pin "LCP") (pinfunction "P2_LCP") (pintype "passive"))
    )
    (net (code "65") (name "unconnected-(ESP-8266-GPIO0-Pad3)") (class "Default")
      (node (ref "ESP-8266") (pin "3") (pinfunction "GPIO0_3") (pintype "passive"))
    )
    (net (code "66") (name "unconnected-(ESP-8266-GPIO2-Pad2)") (class "Default")
      (node (ref "ESP-8266") (pin "2") (pinfunction "GPIO2_2") (pintype "passive"))
    )
    (net (code "67") (name "unconnected-(ESP-8266-GPIO16-Pad7)") (class "Default")
      (node (ref "ESP-8266") (pin "7") (pinfunction "GPIO16_7") (pintype "passive"))
    )
    (net (code "68") (name "unconnected-(J2-DAT1-Pad8)") (class "Default")
      (node (ref "J2") (pin "8") (pinfunction "DAT1_8") (pintype "passive"))
    )
    (net (code "69") (name "unconnected-(J2-DAT2-Pad1)") (class "Default")
      (node (ref "J2") (pin "1") (pinfunction "DAT2_1") (pintype "passive"))
    )
    (net (code "70") (name "unconnected-(LCD-MODULE-NC-Pad23)") (class "Default")
      (node (ref "LCD-MODULE") (pin "23") (pinfunction "NC_23") (pintype "passive"))
    )
    (net (code "71") (name "unconnected-(LCD-MODULE-NC-Pad24)") (class "Default")
      (node (ref "LCD-MODULE") (pin "24") (pinfunction "NC_24") (pintype "passive"))
    )
    (net (code "72") (name "unconnected-(LCD-MODULE-NC-Pad25)") (class "Default")
      (node (ref "LCD-MODULE") (pin "25") (pinfunction "NC_25") (pintype "passive"))
    )
    (net (code "73") (name "unconnected-(LCD-MODULE-NC-Pad27)") (class "Default")
      (node (ref "LCD-MODULE") (pin "27") (pinfunction "NC_27") (pintype "passive"))
    )
    (net (code "74") (name "unconnected-(LCD-MODULE-NC-Pad28)") (class "Default")
      (node (ref "LCD-MODULE") (pin "28") (pinfunction "NC_28") (pintype "passive"))
    )
    (net (code "75") (name "unconnected-(LCD-MODULE-NC-Pad29)") (class "Default")
      (node (ref "LCD-MODULE") (pin "29") (pinfunction "NC_29") (pintype "passive"))
    )
    (net (code "76") (name "unconnected-(LCD-MODULE-NC-Pad30)") (class "Default")
      (node (ref "LCD-MODULE") (pin "30") (pinfunction "NC_30") (pintype "passive"))
    )
    (net (code "77") (name "unconnected-(LCD-MODULE-RESET-Pad37)") (class "Default")
      (node (ref "LCD-MODULE") (pin "37") (pinfunction "RESET_37") (pintype "passive"))
    )
    (net (code "78") (name "unconnected-(LCD-MODULE-SD_CLK-Pad33)") (class "Default")
      (node (ref "LCD-MODULE") (pin "33") (pinfunction "SD_CLK_33") (pintype "passive"))
    )
    (net (code "79") (name "unconnected-(LCD-MODULE-SD_CS-Pad34)") (class "Default")
      (node (ref "LCD-MODULE") (pin "34") (pinfunction "SD_CS_34") (pintype "passive"))
    )
    (net (code "80") (name "unconnected-(LCD-MODULE-SD_MISO-Pad31)") (class "Default")
      (node (ref "LCD-MODULE") (pin "31") (pinfunction "SD_MISO_31") (pintype "passive"))
    )
    (net (code "81") (name "unconnected-(LCD-MODULE-SD_MOSI-Pad32)") (class "Default")
      (node (ref "LCD-MODULE") (pin "32") (pinfunction "SD_MOSI_32") (pintype "passive"))
    )
    (net (code "82") (name "unconnected-(T1-S2-PadLCG1)") (class "Default")
      (node (ref "T1") (pin "LCG1") (pinfunction "S2_LCG1") (pintype "passive"))
    )
  )
)
